# STCAutoDownload.net
KiCad netlist of a schematic drawn in Altium Designer
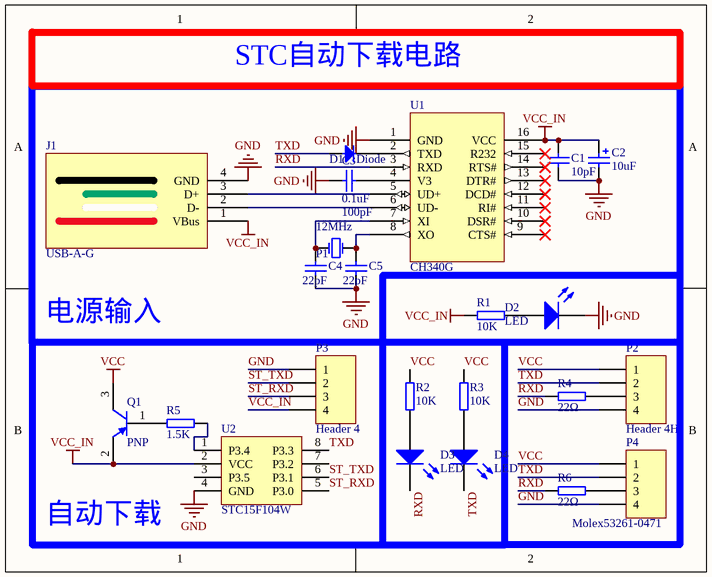
[diagram p0: STCAutoDownload.SchDoc]

(export (version "E")
  (design (tool "Eeschema 10.0.6"))
  (components
    (comp (ref "C1")
      (value "10pF")
      (footprint "0603C")
      (description "Capacitor")
      (fields (field (name "PUBLISHER") "Altium Limited"))
      (libsource (lib "STCAutoDownload") (part "0603C"))
    )
    (comp (ref "C2")
      (value "10uF")
      (footprint "钽电容")
      (description "钽电容")
      (fields (field (name "PUBLISHER") "Altium Limited"))
      (libsource (lib "STCAutoDownload") (part "钽电容"))
    )
    (comp (ref "C3")
      (value "0.1uF")
      (footprint "0603C")
      (description "Capacitor")
      (fields (field (name "ALTIUM_VALUE") "100pF") (field (name "PUBLISHER") "Altium Limited"))
      (libsource (lib "STCAutoDownload") (part "0603C"))
    )
    (comp (ref "C4")
      (value "22pF")
      (footprint "0603C")
      (description "Capacitor")
      (fields (field (name "PUBLISHER") "Altium Limited"))
      (libsource (lib "STCAutoDownload") (part "0603C"))
    )
    (comp (ref "C5")
      (value "22pF")
      (footprint "0603C")
      (description "Capacitor")
      (fields (field (name "PUBLISHER") "Altium Limited"))
      (libsource (lib "STCAutoDownload") (part "0603C"))
    )
    (comp (ref "D1")
      (value "Diode")
      (footprint "Diode")
      (description "二极管")
      (fields (field (name "PUBLISHER") "Altium Limited"))
      (libsource (lib "STCAutoDownload") (part "Diode"))
    )
    (comp (ref "D2")
      (value "LED")
      (footprint "0603LED")
      (description "Typical INFRARED GaAs LED")
      (fields (field (name "PUBLISHER") "Altium Limited"))
      (libsource (lib "STCAutoDownload") (part "0603LED"))
    )
    (comp (ref "D3")
      (value "LED")
      (footprint "0603LED")
      (description "Typical INFRARED GaAs LED")
      (fields (field (name "PUBLISHER") "Altium Limited"))
      (libsource (lib "STCAutoDownload") (part "0603LED"))
    )
    (comp (ref "D4")
      (value "LED")
      (footprint "0603LED")
      (description "Typical INFRARED GaAs LED")
      (fields (field (name "PUBLISHER") "Altium Limited"))
      (libsource (lib "STCAutoDownload") (part "0603LED"))
    )
    (comp (ref "J1")
      (value "USB-A-G")
      (footprint "USB_A_G")
      (description "USB-A 插头")
      (libsource (lib "STCAutoDownload") (part "USB-A-G"))
    )
    (comp (ref "P1")
      (value "12MHz")
      (footprint "XTAL 12M")
      (description "12MHZ振荡器[2PIN]")
      (libsource (lib "STCAutoDownload") (part "XTAL 12M"))
    )
    (comp (ref "P2")
      (value "Header 4H")
      (footprint "Header 4")
      (description "Header, 4-Pin")
      (fields (field (name "PUBLISHER") "Altium Limited"))
      (libsource (lib "STCAutoDownload") (part "Header 4H"))
    )
    (comp (ref "P3")
      (value "Header 4")
      (footprint "Header 4")
      (description "Header, 4-Pin")
      (fields (field (name "PUBLISHER") "Altium Limited"))
      (libsource (lib "STCAutoDownload") (part "Header 4"))
    )
    (comp (ref "P4")
      (value "Molex53261-0471")
      (footprint "Molex53261-0471")
      (description "Header, 4-Pin, Molex53261-0471")
      (fields (field (name "PUBLISHER") "Altium Limited"))
      (libsource (lib "STCAutoDownload") (part "Molex53261-0471"))
    )
    (comp (ref "Q1")
      (value "PNP")
      (footprint "PNP")
      (description "PNP Bipolar Transistor")
      (fields (field (name "PUBLISHER") "Altium Limited"))
      (libsource (lib "STCAutoDownload") (part "PNP"))
    )
    (comp (ref "R1")
      (value "10K")
      (footprint "0603R")
      (description "电阻")
      (libsource (lib "STCAutoDownload") (part "0603R"))
    )
    (comp (ref "R2")
      (value "10K")
      (footprint "0603R")
      (description "电阻")
      (libsource (lib "STCAutoDownload") (part "0603R"))
    )
    (comp (ref "R3")
      (value "10K")
      (footprint "0603R")
      (description "电阻")
      (libsource (lib "STCAutoDownload") (part "0603R"))
    )
    (comp (ref "R4")
      (value "22Ω")
      (footprint "0603R")
      (description "电阻")
      (libsource (lib "STCAutoDownload") (part "0603R"))
    )
    (comp (ref "R5")
      (value "1.5K")
      (footprint "0603R")
      (description "电阻")
      (libsource (lib "STCAutoDownload") (part "0603R"))
    )
    (comp (ref "R6")
      (value "22Ω")
      (footprint "0603R")
      (description "电阻")
      (libsource (lib "STCAutoDownload") (part "0603R"))
    )
    (comp (ref "U1")
      (value "CH340G")
      (footprint "CH340G")
      (description "USB to TTL Serial / UART")
      (libsource (lib "STCAutoDownload") (part "CH340G"))
    )
    (comp (ref "U2")
      (value "STC15F104W")
      (footprint "STC15F104W")
      (libsource (lib "STCAutoDownload") (part "STC15F104W"))
    )
  )
  (nets
    (net (code "1") (name "/RXD") (class "Default")
      (node (ref "D3") (pin "2") (pinfunction "K_2") (pintype "passive"))
      (node (ref "R4") (pin "1") (pinfunction "1_1") (pintype "passive"))
      (node (ref "R6") (pin "1") (pinfunction "1_1") (pintype "passive"))
      (node (ref "U1") (pin "3") (pinfunction "RXD_3") (pintype "input"))
    )
    (net (code "2") (name "/ST_RXD") (class "Default")
      (node (ref "P3") (pin "3") (pinfunction "3_3") (pintype "passive"))
      (node (ref "U2") (pin "5") (pinfunction "P3.0_5") (pintype "passive"))
    )
    (net (code "3") (name "/ST_TXD") (class "Default")
      (node (ref "P3") (pin "2") (pinfunction "2_2") (pintype "passive"))
      (node (ref "U2") (pin "6") (pinfunction "P3.1_6") (pintype "passive"))
    )
    (net (code "4") (name "/TXD") (class "Default")
      (node (ref "D1") (pin "1") (pinfunction "A_1") (pintype "passive"))
      (node (ref "D4") (pin "2") (pinfunction "K_2") (pintype "passive"))
      (node (ref "P2") (pin "2") (pinfunction "2_2") (pintype "passive"))
      (node (ref "P4") (pin "2") (pinfunction "2_2") (pintype "passive"))
      (node (ref "U2") (pin "8") (pinfunction "P3.3_8") (pintype "passive"))
    )
    (net (code "5") (name "GND") (class "Default")
      (node (ref "C1") (pin "1") (pinfunction "1_1") (pintype "passive"))
      (node (ref "C2") (pin "2") (pinfunction "2_2") (pintype "passive"))
      (node (ref "C3") (pin "1") (pinfunction "1_1") (pintype "passive"))
      (node (ref "C4") (pin "1") (pinfunction "1_1") (pintype "passive"))
      (node (ref "C5") (pin "1") (pinfunction "1_1") (pintype "passive"))
      (node (ref "D2") (pin "2") (pinfunction "K_2") (pintype "passive"))
      (node (ref "J1") (pin "4") (pinfunction "GND_4") (pintype "passive"))
      (node (ref "P2") (pin "4") (pinfunction "4_4") (pintype "passive"))
      (node (ref "P3") (pin "1") (pinfunction "1_1") (pintype "passive"))
      (node (ref "P4") (pin "4") (pinfunction "4_4") (pintype "passive"))
      (node (ref "U1") (pin "1") (pinfunction "GND_1") (pintype "power_in"))
      (node (ref "U2") (pin "4") (pinfunction "GND_4") (pintype "passive"))
    )
    (net (code "6") (name "Net-(D1-K)") (class "Default")
      (node (ref "D1") (pin "2") (pinfunction "K_2") (pintype "passive"))
      (node (ref "U1") (pin "2") (pinfunction "TXD_2") (pintype "output"))
    )
    (net (code "7") (name "Net-(D2-A)") (class "Default")
      (node (ref "D2") (pin "1") (pinfunction "A_1") (pintype "passive"))
      (node (ref "R1") (pin "2") (pinfunction "2_2") (pintype "passive"))
    )
    (net (code "8") (name "Net-(D3-A)") (class "Default")
      (node (ref "D3") (pin "1") (pinfunction "A_1") (pintype "passive"))
      (node (ref "R2") (pin "2") (pinfunction "2_2") (pintype "passive"))
    )
    (net (code "9") (name "Net-(D4-A)") (class "Default")
      (node (ref "D4") (pin "1") (pinfunction "A_1") (pintype "passive"))
      (node (ref "R3") (pin "2") (pinfunction "2_2") (pintype "passive"))
    )
    (net (code "10") (name "Net-(J1-D+)") (class "Default")
      (node (ref "J1") (pin "3") (pinfunction "D+_3") (pintype "passive"))
      (node (ref "U1") (pin "5") (pinfunction "UD+_5") (pintype "bidirectional"))
    )
    (net (code "11") (name "Net-(J1-D-)") (class "Default")
      (node (ref "J1") (pin "2") (pinfunction "D-_2") (pintype "passive"))
      (node (ref "U1") (pin "6") (pinfunction "UD-_6") (pintype "bidirectional"))
    )
    (net (code "12") (name "Net-(P1-OSC1)") (class "Default")
      (node (ref "C4") (pin "2") (pinfunction "2_2") (pintype "passive"))
      (node (ref "P1") (pin "1") (pinfunction "OSC1_1") (pintype "passive"))
      (node (ref "U1") (pin "7") (pinfunction "XI_7") (pintype "input"))
    )
    (net (code "13") (name "Net-(P1-OSC2)") (class "Default")
      (node (ref "C5") (pin "2") (pinfunction "2_2") (pintype "passive"))
      (node (ref "P1") (pin "2") (pinfunction "OSC2_2") (pintype "passive"))
      (node (ref "U1") (pin "8") (pinfunction "XO_8") (pintype "output"))
    )
    (net (code "14") (name "Net-(P2-Pad3)") (class "Default")
      (node (ref "P2") (pin "3") (pinfunction "3_3") (pintype "passive"))
      (node (ref "R4") (pin "2") (pinfunction "2_2") (pintype "passive"))
    )
    (net (code "15") (name "Net-(P4-Pad3)") (class "Default")
      (node (ref "P4") (pin "3") (pinfunction "3_3") (pintype "passive"))
      (node (ref "R6") (pin "2") (pinfunction "2_2") (pintype "passive"))
    )
    (net (code "16") (name "Net-(Q1-B)") (class "Default")
      (node (ref "Q1") (pin "1") (pinfunction "B_1") (pintype "passive"))
      (node (ref "R5") (pin "1") (pinfunction "1_1") (pintype "passive"))
    )
    (net (code "17") (name "Net-(U1-V3)") (class "Default")
      (node (ref "C3") (pin "2") (pinfunction "2_2") (pintype "passive"))
      (node (ref "U1") (pin "4") (pinfunction "V3_4") (pintype "power_in"))
    )
    (net (code "18") (name "Net-(U2-P3.4)") (class "Default")
      (node (ref "R5") (pin "2") (pinfunction "2_2") (pintype "passive"))
      (node (ref "U2") (pin "1") (pinfunction "P3.4_1") (pintype "passive"))
    )
    (net (code "19") (name "VCC") (class "Default")
      (node (ref "P2") (pin "1") (pinfunction "1_1") (pintype "passive"))
      (node (ref "P4") (pin "1") (pinfunction "1_1") (pintype "passive"))
      (node (ref "Q1") (pin "3") (pinfunction "C_3") (pintype "passive"))
      (node (ref "R2") (pin "1") (pinfunction "1_1") (pintype "passive"))
      (node (ref "R3") (pin "1") (pinfunction "1_1") (pintype "passive"))
    )
    (net (code "20") (name "VCC_IN") (class "Default")
      (node (ref "C1") (pin "2") (pinfunction "2_2") (pintype "passive"))
      (node (ref "C2") (pin "1") (pinfunction "1_1") (pintype "passive"))
      (node (ref "J1") (pin "1") (pinfunction "VBus_1") (pintype "passive"))
      (node (ref "P3") (pin "4") (pinfunction "4_4") (pintype "passive"))
      (node (ref "Q1") (pin "2") (pinfunction "E_2") (pintype "passive"))
      (node (ref "R1") (pin "1") (pinfunction "1_1") (pintype "passive"))
      (node (ref "U1") (pin "16") (pinfunction "VCC_16") (pintype "power_in"))
      (node (ref "U2") (pin "2") (pinfunction "VCC_2") (pintype "passive"))
    )
    (net (code "21") (name "unconnected-(U1-CTS#-Pad9)") (class "Default")
      (node (ref "U1") (pin "9") (pinfunction "CTS#_9") (pintype "input+no_connect"))
    )
    (net (code "22") (name "unconnected-(U1-DCD#-Pad12)") (class "Default")
      (node (ref "U1") (pin "12") (pinfunction "DCD#_12") (pintype "input+no_connect"))
    )
    (net (code "23") (name "unconnected-(U1-DSR#-Pad10)") (class "Default")
      (node (ref "U1") (pin "10") (pinfunction "DSR#_10") (pintype "input+no_connect"))
    )
    (net (code "24") (name "unconnected-(U1-DTR#-Pad13)") (class "Default")
      (node (ref "U1") (pin "13") (pinfunction "DTR#_13") (pintype "output+no_connect"))
    )
    (net (code "25") (name "unconnected-(U1-R232-Pad15)") (class "Default")
      (node (ref "U1") (pin "15") (pinfunction "R232_15") (pintype "input+no_connect"))
    )
    (net (code "26") (name "unconnected-(U1-RI#-Pad11)") (class "Default")
      (node (ref "U1") (pin "11") (pinfunction "RI#_11") (pintype "input+no_connect"))
    )
    (net (code "27") (name "unconnected-(U1-RTS#-Pad14)") (class "Default")
      (node (ref "U1") (pin "14") (pinfunction "RTS#_14") (pintype "output+no_connect"))
    )
    (net (code "28") (name "unconnected-(U2-P3.2-Pad7)") (class "Default")
      (node (ref "U2") (pin "7") (pinfunction "P3.2_7") (pintype "passive"))
    )
    (net (code "29") (name "unconnected-(U2-P3.5-Pad3)") (class "Default")
      (node (ref "U2") (pin "3") (pinfunction "P3.5_3") (pintype "passive"))
    )
  )
)
